# hv_breakout.net
KiCad netlist of a schematic drawn in Altium Designer
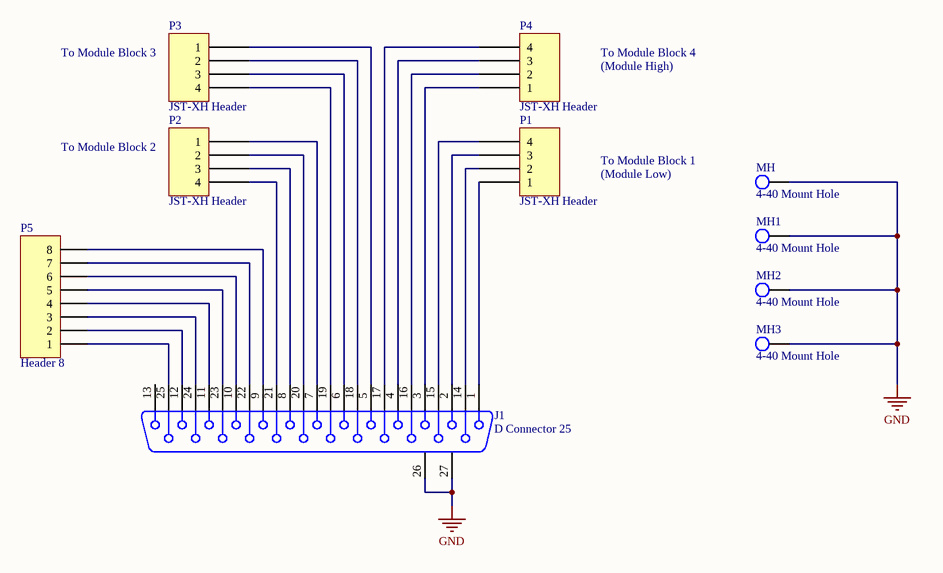
[diagram p0: hv_breakout.SchDoc]

(export (version "E")
  (design (tool "Eeschema 10.0.6"))
  (components
    (comp (ref "J1")
      (value "D Connector 25")
      (footprint "DSUB1.385-2H25A")
      (description "Receptacle Assembly, 25 Position, Right Angle")
      (fields (field (name "PUBLISHER") "Altium Limited"))
      (libsource (lib "connector") (part "D Connector 25"))
    )
    (comp (ref "MH")
      (value "4-40 Mount Hole")
      (footprint "MH")
      (libsource (lib "misc") (part "4-40 Mount Hole"))
    )
    (comp (ref "MH1")
      (value "4-40 Mount Hole")
      (footprint "MH")
      (libsource (lib "misc") (part "4-40 Mount Hole"))
    )
    (comp (ref "MH2")
      (value "4-40 Mount Hole")
      (footprint "MH")
      (libsource (lib "misc") (part "4-40 Mount Hole"))
    )
    (comp (ref "MH3")
      (value "4-40 Mount Hole")
      (footprint "MH")
      (libsource (lib "misc") (part "4-40 Mount Hole"))
    )
    (comp (ref "P1")
      (value "JST-XH Header")
      (footprint "JST - XH 4 Pos")
      (description "JST-XH CONN HEADER VERT 4POS 2.5MM")
      (fields (field (name "MANUFACTURER") "JST Sales America"))
      (libsource (lib "shelby_temp_new") (part "JST-XH Header"))
    )
    (comp (ref "P2")
      (value "JST-XH Header")
      (footprint "JST - XH 4 Pos")
      (description "JST-XH CONN HEADER VERT 4POS 2.5MM")
      (fields (field (name "MANUFACTURER") "JST Sales America"))
      (libsource (lib "") (part "JST-XH Header_1"))
    )
    (comp (ref "P3")
      (value "JST-XH Header")
      (footprint "JST - XH 4 Pos")
      (description "JST-XH CONN HEADER VERT 4POS 2.5MM")
      (fields (field (name "MANUFACTURER") "JST Sales America"))
      (libsource (lib "") (part "JST-XH Header_1"))
    )
    (comp (ref "P4")
      (value "JST-XH Header")
      (footprint "JST - XH 4 Pos")
      (description "JST-XH CONN HEADER VERT 4POS 2.5MM")
      (fields (field (name "MANUFACTURER") "JST Sales America"))
      (libsource (lib "shelby_temp_new") (part "JST-XH Header"))
    )
    (comp (ref "P5")
      (value "Header 8")
      (footprint "Pin Header 1x8 TH Pitch 2.54mm")
      (description "Header, 8-Pin")
      (fields (field (name "PUBLISHER") "Altium Limited"))
      (libsource (lib "connector") (part "Header 8"))
    )
  )
  (nets
    (net (code "1") (name "GND") (class "Default")
      (node (ref "J1") (pin "26") (pinfunction "MH1_26") (pintype "passive"))
      (node (ref "J1") (pin "27") (pinfunction "MH2_27") (pintype "passive"))
      (node (ref "MH") (pin "46") (pinfunction "46_46") (pintype "passive"))
      (node (ref "MH1") (pin "46") (pinfunction "46_46") (pintype "passive"))
      (node (ref "MH2") (pin "46") (pinfunction "46_46") (pintype "passive"))
      (node (ref "MH3") (pin "46") (pinfunction "46_46") (pintype "passive"))
    )
    (net (code "2") (name "Net-(J1-Pad1)") (class "Default")
      (node (ref "J1") (pin "1") (pinfunction "1_1") (pintype "passive"))
      (node (ref "P1") (pin "1") (pinfunction "1_1") (pintype "passive"))
    )
    (net (code "3") (name "Net-(J1-Pad2)") (class "Default")
      (node (ref "J1") (pin "2") (pinfunction "2_2") (pintype "passive"))
      (node (ref "P1") (pin "3") (pinfunction "3_3") (pintype "passive"))
    )
    (net (code "4") (name "Net-(J1-Pad3)") (class "Default")
      (node (ref "J1") (pin "3") (pinfunction "3_3") (pintype "passive"))
      (node (ref "P4") (pin "1") (pinfunction "1_1") (pintype "passive"))
    )
    (net (code "5") (name "Net-(J1-Pad4)") (class "Default")
      (node (ref "J1") (pin "4") (pinfunction "4_4") (pintype "passive"))
      (node (ref "P4") (pin "3") (pinfunction "3_3") (pintype "passive"))
    )
    (net (code "6") (name "Net-(J1-Pad5)") (class "Default")
      (node (ref "J1") (pin "5") (pinfunction "5_5") (pintype "passive"))
      (node (ref "P3") (pin "1") (pinfunction "1_1") (pintype "passive"))
    )
    (net (code "7") (name "Net-(J1-Pad6)") (class "Default")
      (node (ref "J1") (pin "6") (pinfunction "6_6") (pintype "passive"))
      (node (ref "P3") (pin "3") (pinfunction "3_3") (pintype "passive"))
    )
    (net (code "8") (name "Net-(J1-Pad7)") (class "Default")
      (node (ref "J1") (pin "7") (pinfunction "7_7") (pintype "passive"))
      (node (ref "P2") (pin "1") (pinfunction "1_1") (pintype "passive"))
    )
    (net (code "9") (name "Net-(J1-Pad8)") (class "Default")
      (node (ref "J1") (pin "8") (pinfunction "8_8") (pintype "passive"))
      (node (ref "P2") (pin "3") (pinfunction "3_3") (pintype "passive"))
    )
    (net (code "10") (name "Net-(J1-Pad9)") (class "Default")
      (node (ref "J1") (pin "9") (pinfunction "9_9") (pintype "passive"))
      (node (ref "P5") (pin "8") (pinfunction "8_8") (pintype "passive"))
    )
    (net (code "11") (name "Net-(J1-Pad10)") (class "Default")
      (node (ref "J1") (pin "10") (pinfunction "10_10") (pintype "passive"))
      (node (ref "P5") (pin "6") (pinfunction "6_6") (pintype "passive"))
    )
    (net (code "12") (name "Net-(J1-Pad11)") (class "Default")
      (node (ref "J1") (pin "11") (pinfunction "11_11") (pintype "passive"))
      (node (ref "P5") (pin "4") (pinfunction "4_4") (pintype "passive"))
    )
    (net (code "13") (name "Net-(J1-Pad12)") (class "Default")
      (node (ref "J1") (pin "12") (pinfunction "12_12") (pintype "passive"))
      (node (ref "P5") (pin "2") (pinfunction "2_2") (pintype "passive"))
    )
    (net (code "14") (name "Net-(J1-Pad14)") (class "Default")
      (node (ref "J1") (pin "14") (pinfunction "14_14") (pintype "passive"))
      (node (ref "P1") (pin "2") (pinfunction "2_2") (pintype "passive"))
    )
    (net (code "15") (name "Net-(J1-Pad15)") (class "Default")
      (node (ref "J1") (pin "15") (pinfunction "15_15") (pintype "passive"))
      (node (ref "P1") (pin "4") (pinfunction "4_4") (pintype "passive"))
    )
    (net (code "16") (name "Net-(J1-Pad16)") (class "Default")
      (node (ref "J1") (pin "16") (pinfunction "16_16") (pintype "passive"))
      (node (ref "P4") (pin "2") (pinfunction "2_2") (pintype "passive"))
    )
    (net (code "17") (name "Net-(J1-Pad17)") (class "Default")
      (node (ref "J1") (pin "17") (pinfunction "17_17") (pintype "passive"))
      (node (ref "P4") (pin "4") (pinfunction "4_4") (pintype "passive"))
    )
    (net (code "18") (name "Net-(J1-Pad18)") (class "Default")
      (node (ref "J1") (pin "18") (pinfunction "18_18") (pintype "passive"))
      (node (ref "P3") (pin "2") (pinfunction "2_2") (pintype "passive"))
    )
    (net (code "19") (name "Net-(J1-Pad19)") (class "Default")
      (node (ref "J1") (pin "19") (pinfunction "19_19") (pintype "passive"))
      (node (ref "P3") (pin "4") (pinfunction "4_4") (pintype "passive"))
    )
    (net (code "20") (name "Net-(J1-Pad20)") (class "Default")
      (node (ref "J1") (pin "20") (pinfunction "20_20") (pintype "passive"))
      (node (ref "P2") (pin "2") (pinfunction "2_2") (pintype "passive"))
    )
    (net (code "21") (name "Net-(J1-Pad21)") (class "Default")
      (node (ref "J1") (pin "21") (pinfunction "21_21") (pintype "passive"))
      (node (ref "P2") (pin "4") (pinfunction "4_4") (pintype "passive"))
    )
    (net (code "22") (name "Net-(J1-Pad22)") (class "Default")
      (node (ref "J1") (pin "22") (pinfunction "22_22") (pintype "passive"))
      (node (ref "P5") (pin "7") (pinfunction "7_7") (pintype "passive"))
    )
    (net (code "23") (name "Net-(J1-Pad23)") (class "Default")
      (node (ref "J1") (pin "23") (pinfunction "23_23") (pintype "passive"))
      (node (ref "P5") (pin "5") (pinfunction "5_5") (pintype "passive"))
    )
    (net (code "24") (name "Net-(J1-Pad24)") (class "Default")
      (node (ref "J1") (pin "24") (pinfunction "24_24") (pintype "passive"))
      (node (ref "P5") (pin "3") (pinfunction "3_3") (pintype "passive"))
    )
    (net (code "25") (name "Net-(J1-Pad25)") (class "Default")
      (node (ref "J1") (pin "25") (pinfunction "25_25") (pintype "passive"))
      (node (ref "P5") (pin "1") (pinfunction "1_1") (pintype "passive"))
    )
    (net (code "26") (name "unconnected-(J1-Pad13)") (class "Default")
      (node (ref "J1") (pin "13") (pinfunction "13_13") (pintype "passive"))
    )
  )
)
